# SimpleAudio_Amplifier.net
KiCad netlist of a schematic drawn in EAGLE
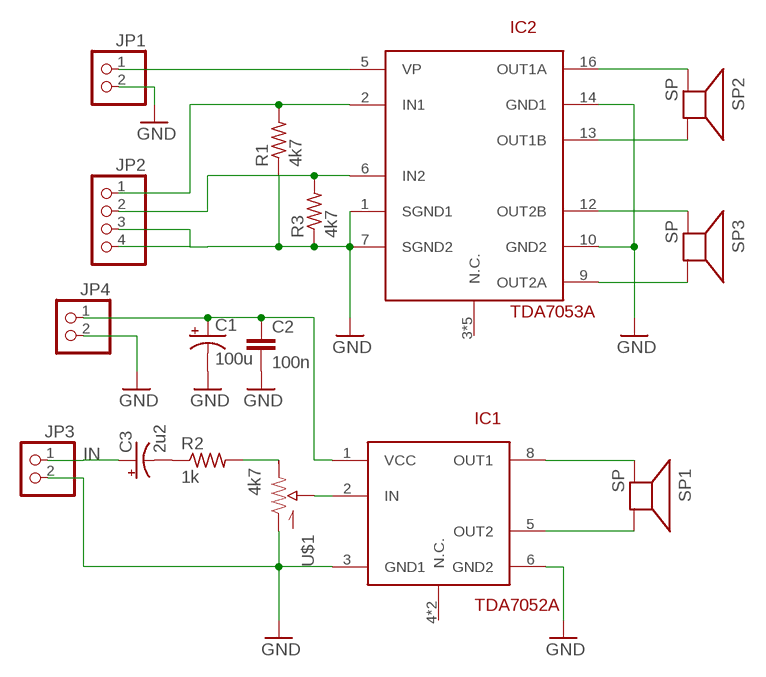
[diagram p0: schematic, sheet 1]

(export (version "E")
  (design (tool "Eeschema 10.0.6"))
  (components
    (comp (ref "C1")
      (value "100u")
      (footprint "eagle-import:CPOL-RADIAL-100UF-25V")
      (libsource (lib "eagle-import") (part "CAP_POLPTH1"))
    )
    (comp (ref "C2")
      (value "100n")
      (footprint "eagle-import:CAP-PTH-SMALL2")
      (libsource (lib "eagle-import") (part "CAPPTH2"))
    )
    (comp (ref "C3")
      (value "2u2")
      (footprint "eagle-import:CPOL-RADIAL-100UF-25V")
      (libsource (lib "eagle-import") (part "CAP_POLPTH1"))
    )
    (comp (ref "IC1")
      (value "TDA7052A")
      (footprint "eagle-import:DIL08")
      (libsource (lib "eagle-import") (part "TDA7052A"))
    )
    (comp (ref "IC2")
      (value "TDA7053A")
      (footprint "eagle-import:DIL16")
      (libsource (lib "eagle-import") (part "TDA7053A"))
    )
    (comp (ref "JP1")
      (value "PINHD-1X2")
      (footprint "eagle-import:1X02")
      (libsource (lib "eagle-import") (part "PINHD-1X2"))
    )
    (comp (ref "JP2")
      (value "PINHD-1X4")
      (footprint "eagle-import:1X04")
      (libsource (lib "eagle-import") (part "PINHD-1X4"))
    )
    (comp (ref "JP3")
      (value "PINHD-1X2")
      (footprint "eagle-import:1X02")
      (libsource (lib "eagle-import") (part "PINHD-1X2"))
    )
    (comp (ref "JP4")
      (value "PINHD-1X2")
      (footprint "eagle-import:1X02")
      (libsource (lib "eagle-import") (part "PINHD-1X2"))
    )
    (comp (ref "R1")
      (value "4k7")
      (footprint "eagle-import:0204_5")
      (libsource (lib "eagle-import") (part "R-US_0204/5"))
    )
    (comp (ref "R2")
      (value "1k")
      (footprint "eagle-import:0204_5")
      (libsource (lib "eagle-import") (part "R-US_0204/5"))
    )
    (comp (ref "R3")
      (value "4k7")
      (footprint "eagle-import:0204_5")
      (libsource (lib "eagle-import") (part "R-US_0204/5"))
    )
    (comp (ref "SP1")
      (value "SP")
      (footprint "eagle-import:PS12")
      (libsource (lib "eagle-import") (part "SP"))
    )
    (comp (ref "SP2")
      (value "SP")
      (footprint "eagle-import:PS12")
      (libsource (lib "eagle-import") (part "SP"))
    )
    (comp (ref "SP3")
      (value "SP")
      (footprint "eagle-import:PS12")
      (libsource (lib "eagle-import") (part "SP"))
    )
    (comp (ref "U$1")
      (value "4k7")
      (footprint "eagle-import:POT_ALPHA_RV16AF-20")
      (libsource (lib "eagle-import") (part "POT-RV16AF-20"))
    )
  )
  (nets
    (net (code "1") (name "/IN") (class "Default")
      (node (ref "C3") (pin "1") (pinfunction "+_1") (pintype "passive"))
      (node (ref "JP3") (pin "1") (pinfunction "1_1") (pintype "passive"))
    )
    (net (code "2") (name "GND") (class "Default")
      (node (ref "C1") (pin "2") (pinfunction "-_2") (pintype "passive"))
      (node (ref "C2") (pin "2") (pinfunction "2_2") (pintype "passive"))
      (node (ref "IC1") (pin "3") (pinfunction "GND1_3") (pintype "power_in"))
      (node (ref "IC1") (pin "6") (pinfunction "GND2_6") (pintype "power_in"))
      (node (ref "IC2") (pin "1") (pinfunction "SGND1_1") (pintype "power_in"))
      (node (ref "IC2") (pin "10") (pinfunction "GND2_10") (pintype "power_in"))
      (node (ref "IC2") (pin "14") (pinfunction "GND1_14") (pintype "power_in"))
      (node (ref "IC2") (pin "7") (pinfunction "SGND2_7") (pintype "power_in"))
      (node (ref "JP1") (pin "2") (pinfunction "2_2") (pintype "passive"))
      (node (ref "JP2") (pin "3") (pinfunction "3_3") (pintype "passive"))
      (node (ref "JP2") (pin "4") (pinfunction "4_4") (pintype "passive"))
      (node (ref "JP3") (pin "2") (pinfunction "2_2") (pintype "passive"))
      (node (ref "JP4") (pin "2") (pinfunction "2_2") (pintype "passive"))
      (node (ref "R1") (pin "1") (pinfunction "1_1") (pintype "passive"))
      (node (ref "R3") (pin "1") (pinfunction "1_1") (pintype "passive"))
      (node (ref "U$1") (pin "1") (pinfunction "A_1") (pintype "passive"))
    )
    (net (code "3") (name "Net-(C1-+)") (class "Default")
      (node (ref "C1") (pin "1") (pinfunction "+_1") (pintype "passive"))
      (node (ref "C2") (pin "1") (pinfunction "1_1") (pintype "passive"))
      (node (ref "IC1") (pin "1") (pinfunction "VCC_1") (pintype "power_in"))
      (node (ref "JP4") (pin "1") (pinfunction "1_1") (pintype "passive"))
    )
    (net (code "4") (name "Net-(C3--)") (class "Default")
      (node (ref "C3") (pin "2") (pinfunction "-_2") (pintype "passive"))
      (node (ref "R2") (pin "1") (pinfunction "1_1") (pintype "passive"))
    )
    (net (code "5") (name "Net-(IC1-IN)") (class "Default")
      (node (ref "IC1") (pin "2") (pinfunction "IN_2") (pintype "input"))
      (node (ref "U$1") (pin "2") (pinfunction "S_2") (pintype "passive"))
    )
    (net (code "6") (name "Net-(IC1-OUT1)") (class "Default")
      (node (ref "IC1") (pin "8") (pinfunction "OUT1_8") (pintype "output"))
      (node (ref "SP1") (pin "P$1") (pinfunction "+_P$1") (pintype "passive"))
    )
    (net (code "7") (name "Net-(IC1-OUT2)") (class "Default")
      (node (ref "IC1") (pin "5") (pinfunction "OUT2_5") (pintype "output"))
      (node (ref "SP1") (pin "P$2") (pinfunction "-_P$2") (pintype "passive"))
    )
    (net (code "8") (name "Net-(IC2-IN1)") (class "Default")
      (node (ref "IC2") (pin "2") (pinfunction "IN1_2") (pintype "input"))
      (node (ref "JP2") (pin "1") (pinfunction "1_1") (pintype "passive"))
      (node (ref "R1") (pin "2") (pinfunction "2_2") (pintype "passive"))
    )
    (net (code "9") (name "Net-(IC2-IN2)") (class "Default")
      (node (ref "IC2") (pin "6") (pinfunction "IN2_6") (pintype "input"))
      (node (ref "JP2") (pin "2") (pinfunction "2_2") (pintype "passive"))
      (node (ref "R3") (pin "2") (pinfunction "2_2") (pintype "passive"))
    )
    (net (code "10") (name "Net-(IC2-OUT1A)") (class "Default")
      (node (ref "IC2") (pin "16") (pinfunction "OUT1A_16") (pintype "output"))
      (node (ref "SP2") (pin "P$1") (pinfunction "+_P$1") (pintype "passive"))
    )
    (net (code "11") (name "Net-(IC2-OUT1B)") (class "Default")
      (node (ref "IC2") (pin "13") (pinfunction "OUT1B_13") (pintype "output"))
      (node (ref "SP2") (pin "P$2") (pinfunction "-_P$2") (pintype "passive"))
    )
    (net (code "12") (name "Net-(IC2-OUT2A)") (class "Default")
      (node (ref "IC2") (pin "9") (pinfunction "OUT2A_9") (pintype "output"))
      (node (ref "SP3") (pin "P$2") (pinfunction "-_P$2") (pintype "passive"))
    )
    (net (code "13") (name "Net-(IC2-OUT2B)") (class "Default")
      (node (ref "IC2") (pin "12") (pinfunction "OUT2B_12") (pintype "output"))
      (node (ref "SP3") (pin "P$1") (pinfunction "+_P$1") (pintype "passive"))
    )
    (net (code "14") (name "Net-(IC2-VP)") (class "Default")
      (node (ref "IC2") (pin "5") (pinfunction "VP_5") (pintype "bidirectional"))
      (node (ref "JP1") (pin "1") (pinfunction "1_1") (pintype "passive"))
    )
    (net (code "15") (name "Net-(U$1-E)") (class "Default")
      (node (ref "R2") (pin "2") (pinfunction "2_2") (pintype "passive"))
      (node (ref "U$1") (pin "3") (pinfunction "E_3") (pintype "passive"))
    )
    (net (code "16") (name "unconnected-(IC1-N.C.-Pad4)") (class "Default")
      (node (ref "IC1") (pin "4") (pinfunction "N.C._4") (pintype "no_connect"))
    )
    (net (code "17") (name "unconnected-(IC1-N.C.-Pad7)") (class "Default")
      (node (ref "IC1") (pin "7") (pinfunction "N.C._7") (pintype "no_connect"))
    )
    (net (code "18") (name "unconnected-(IC2-N.C.-Pad3)") (class "Default")
      (node (ref "IC2") (pin "3") (pinfunction "N.C._3") (pintype "no_connect"))
    )
    (net (code "19") (name "unconnected-(IC2-N.C.-Pad4)") (class "Default")
      (node (ref "IC2") (pin "4") (pinfunction "N.C._4") (pintype "no_connect"))
    )
    (net (code "20") (name "unconnected-(IC2-N.C.-Pad8)") (class "Default")
      (node (ref "IC2") (pin "8") (pinfunction "N.C._8") (pintype "no_connect"))
    )
    (net (code "21") (name "unconnected-(IC2-N.C.-Pad11)") (class "Default")
      (node (ref "IC2") (pin "11") (pinfunction "N.C._11") (pintype "no_connect"))
    )
    (net (code "22") (name "unconnected-(IC2-N.C.-Pad15)") (class "Default")
      (node (ref "IC2") (pin "15") (pinfunction "N.C._15") (pintype "no_connect"))
    )
  )
)
